# LED_Validation_Board_pg_2.net
KiCad netlist of a schematic drawn in Altium Designer
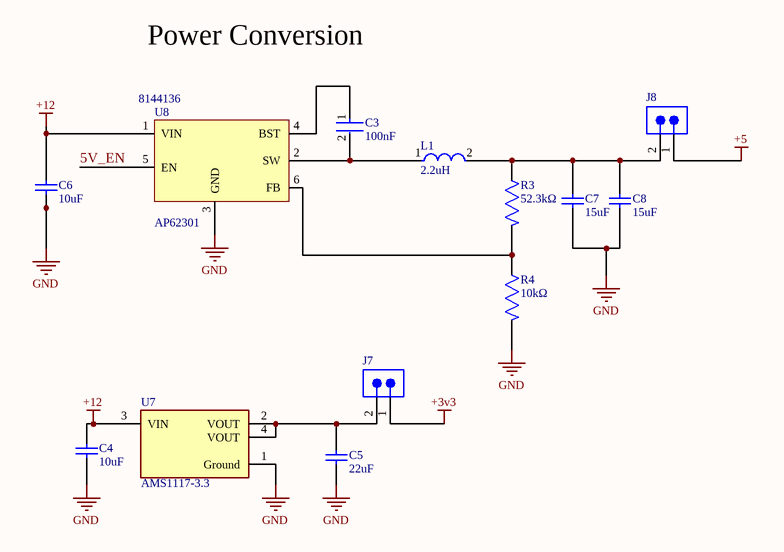
[diagram p0: LED_Validation_Board_pg_2.SchDoc]

(export (version "E")
  (design (tool "Eeschema 10.0.6"))
  (components
    (comp (ref "C3")
      (value "100nF")
      (footprint "FP-C0402-BB-MFG")
      (description "CAP CER 0.1UF 10V X5R 0402")
      (fields (field (name "MANUFACTURER") "Kemet") (field (name "TOLERANCE") "0.1"))
      (libsource (lib "Altium Content Vault") (part "b4654b650e69147ec39a6b967a45e02"))
    )
    (comp (ref "C4")
      (value "10uF")
      (footprint "0805 PACKAGE")
      (description "Chip Multilayer Ceramic Capacitors for General Purpose, 0805, 10uF, X5R, 15%, 10%, 16V")
      (libsource (lib "LED_Validation_Sch_Lib") (part "Capacitor"))
    )
    (comp (ref "C5")
      (value "22uF")
      (footprint "0603 PACKAGE")
      (description "Chip Multilayer Ceramic Capacitors for General Purpose, 0603, 22uF, X5R, 15%, 20%, 10V")
      (libsource (lib "LED_Validation_Sch_Lib") (part "Capacitor"))
    )
    (comp (ref "C6")
      (value "10uF")
      (footprint "0805 PACKAGE")
      (description "Chip Multilayer Ceramic Capacitors for General Purpose, 0805, 10uF, X5R, 15%, 10%, 16V")
      (libsource (lib "LED_Validation_Sch_Lib") (part "Capacitor"))
    )
    (comp (ref "C7")
      (value "15uF")
      (footprint "0603 PACKAGE")
      (description "Chip Multilayer Ceramic Capacitors for General Purpose, 0603, 15uF, X5R, 15%, 20%, 10V")
      (libsource (lib "LED_Validation_Sch_Lib") (part "Capacitor"))
    )
    (comp (ref "C8")
      (value "15uF")
      (footprint "0603 PACKAGE")
      (description "Chip Multilayer Ceramic Capacitors for General Purpose, 0603, 15uF, X5R, 15%, 20%, 10V")
      (libsource (lib "LED_Validation_Sch_Lib") (part "Capacitor"))
    )
    (comp (ref "J7")
      (value "TSW-102-26-F-S")
      (footprint "SMTC-TSW-102-26-XX-S")
      (description "0.025\" SQ Post Header, Through-hole, Vertical, -55 to 125 degC, 2.54 mm Pitch, 2-Pin, Male, RoHS")
      (fields (field (name "MANUFACTURER") "Samtec"))
      (libsource (lib "Altium Content Vault") (part "SMTC-TSW-102-X-X-S-X"))
    )
    (comp (ref "J8")
      (value "TSW-102-26-F-S")
      (footprint "SMTC-TSW-102-26-XX-S")
      (description "0.025\" SQ Post Header, Through-hole, Vertical, -55 to 125 degC, 2.54 mm Pitch, 2-Pin, Male, RoHS")
      (fields (field (name "MANUFACTURER") "Samtec"))
      (libsource (lib "Altium Content Vault") (part "SMTC-TSW-102-X-X-S-X"))
    )
    (comp (ref "L1")
      (value "2.2uH")
      (footprint "FP-IHLP-1212BZ-11-MFG")
      (description "FIXED IND 2.2UH 3A 46 MOHM SMD")
      (fields (field (name "TOLERANCE") "20%"))
      (libsource (lib "Altium Content Vault") (part "725321dda6339637d4d059423bc1c3c"))
    )
    (comp (ref "R3")
      (value "52.3kΩ")
      (footprint "0402 PACKAGE")
      (description "RES 10K OHM 1% 1/16W 0402")
      (libsource (lib "LED_Validation_Sch_Lib") (part "Resistor"))
    )
    (comp (ref "R4")
      (value "10kΩ")
      (footprint "0402 PACKAGE")
      (description "RES 10K OHM 1% 1/16W 0402")
      (libsource (lib "LED_Validation_Sch_Lib") (part "Resistor"))
    )
    (comp (ref "U7")
      (value "AMS1117-3.3")
      (footprint "FP-AMS1117-IPC_C")
      (description "LDO Voltage Regulators 1A, 3.3V")
      (fields
        (field (name "OCTOPART") "https://octopart.com/ams1117-3.3-advanced+monolithic+systems-25899300")
        (field (name "MANUFACTURER") "Advanced Monolithic Systems")
      )
      (libsource (lib "Altium Content Vault") (part "8bdbb5f8e77002000e30dd2845d0354"))
    )
    (comp (ref "U8")
      (value "AP62301")
      (footprint "AP62301")
      (description "Buck Converter \r\nSOT-563")
      (fields (field (name "SUPPLIER PART NUMBER 1") "8144136"))
      (libsource (lib "LED_Module_Schematic_Library") (part "AP62301"))
    )
  )
  (nets
    (net (code "1") (name "+3v3") (class "Default")
      (node (ref "J7") (pin "1") (pinfunction "1_1") (pintype "passive"))
    )
    (net (code "2") (name "+5") (class "Default")
      (node (ref "J8") (pin "1") (pinfunction "1_1") (pintype "passive"))
    )
    (net (code "3") (name "+12") (class "Default")
      (node (ref "C4") (pin "2") (pinfunction "2_2") (pintype "passive"))
      (node (ref "C6") (pin "2") (pinfunction "2_2") (pintype "passive"))
      (node (ref "U7") (pin "3") (pinfunction "VIN_3") (pintype "power_in"))
      (node (ref "U8") (pin "1") (pinfunction "VIN_1") (pintype "passive"))
    )
    (net (code "4") (name "/5V_EN") (class "Default")
      (node (ref "U8") (pin "5") (pinfunction "EN_5") (pintype "passive"))
    )
    (net (code "5") (name "GND") (class "Default")
      (node (ref "C4") (pin "1") (pinfunction "1_1") (pintype "passive"))
      (node (ref "C5") (pin "1") (pinfunction "1_1") (pintype "passive"))
      (node (ref "C6") (pin "1") (pinfunction "1_1") (pintype "passive"))
      (node (ref "C7") (pin "1") (pinfunction "1_1") (pintype "passive"))
      (node (ref "C8") (pin "1") (pinfunction "1_1") (pintype "passive"))
      (node (ref "R4") (pin "2") (pinfunction "2_2") (pintype "passive"))
      (node (ref "U7") (pin "1") (pinfunction "Ground_1") (pintype "power_in"))
      (node (ref "U8") (pin "3") (pinfunction "GND_3") (pintype "passive"))
    )
    (net (code "6") (name "Net-(C5-Pad2)") (class "Default")
      (node (ref "C5") (pin "2") (pinfunction "2_2") (pintype "passive"))
      (node (ref "J7") (pin "2") (pinfunction "2_2") (pintype "passive"))
      (node (ref "U7") (pin "2") (pinfunction "VOUT_2") (pintype "passive"))
      (node (ref "U7") (pin "4") (pinfunction "VOUT_4") (pintype "passive"))
    )
    (net (code "7") (name "Net-(C7-Pad2)") (class "Default")
      (node (ref "C7") (pin "2") (pinfunction "2_2") (pintype "passive"))
      (node (ref "C8") (pin "2") (pinfunction "2_2") (pintype "passive"))
      (node (ref "J8") (pin "2") (pinfunction "2_2") (pintype "passive"))
      (node (ref "L1") (pin "2") (pinfunction "2_2") (pintype "passive"))
      (node (ref "R3") (pin "1") (pinfunction "1_1") (pintype "passive"))
    )
    (net (code "8") (name "Net-(U8-BST)") (class "Default")
      (node (ref "C3") (pin "1") (pinfunction "1_1") (pintype "passive"))
      (node (ref "U8") (pin "4") (pinfunction "BST_4") (pintype "passive"))
    )
    (net (code "9") (name "Net-(U8-FB)") (class "Default")
      (node (ref "R3") (pin "2") (pinfunction "2_2") (pintype "passive"))
      (node (ref "R4") (pin "1") (pinfunction "1_1") (pintype "passive"))
      (node (ref "U8") (pin "6") (pinfunction "FB_6") (pintype "passive"))
    )
    (net (code "10") (name "Net-(U8-SW)") (class "Default")
      (node (ref "C3") (pin "2") (pinfunction "2_2") (pintype "passive"))
      (node (ref "L1") (pin "1") (pinfunction "1_1") (pintype "passive"))
      (node (ref "U8") (pin "2") (pinfunction "SW_2") (pintype "passive"))
    )
  )
)
